# SenseBox-Eye_v1_3.net
KiCad netlist of a schematic drawn in EAGLE
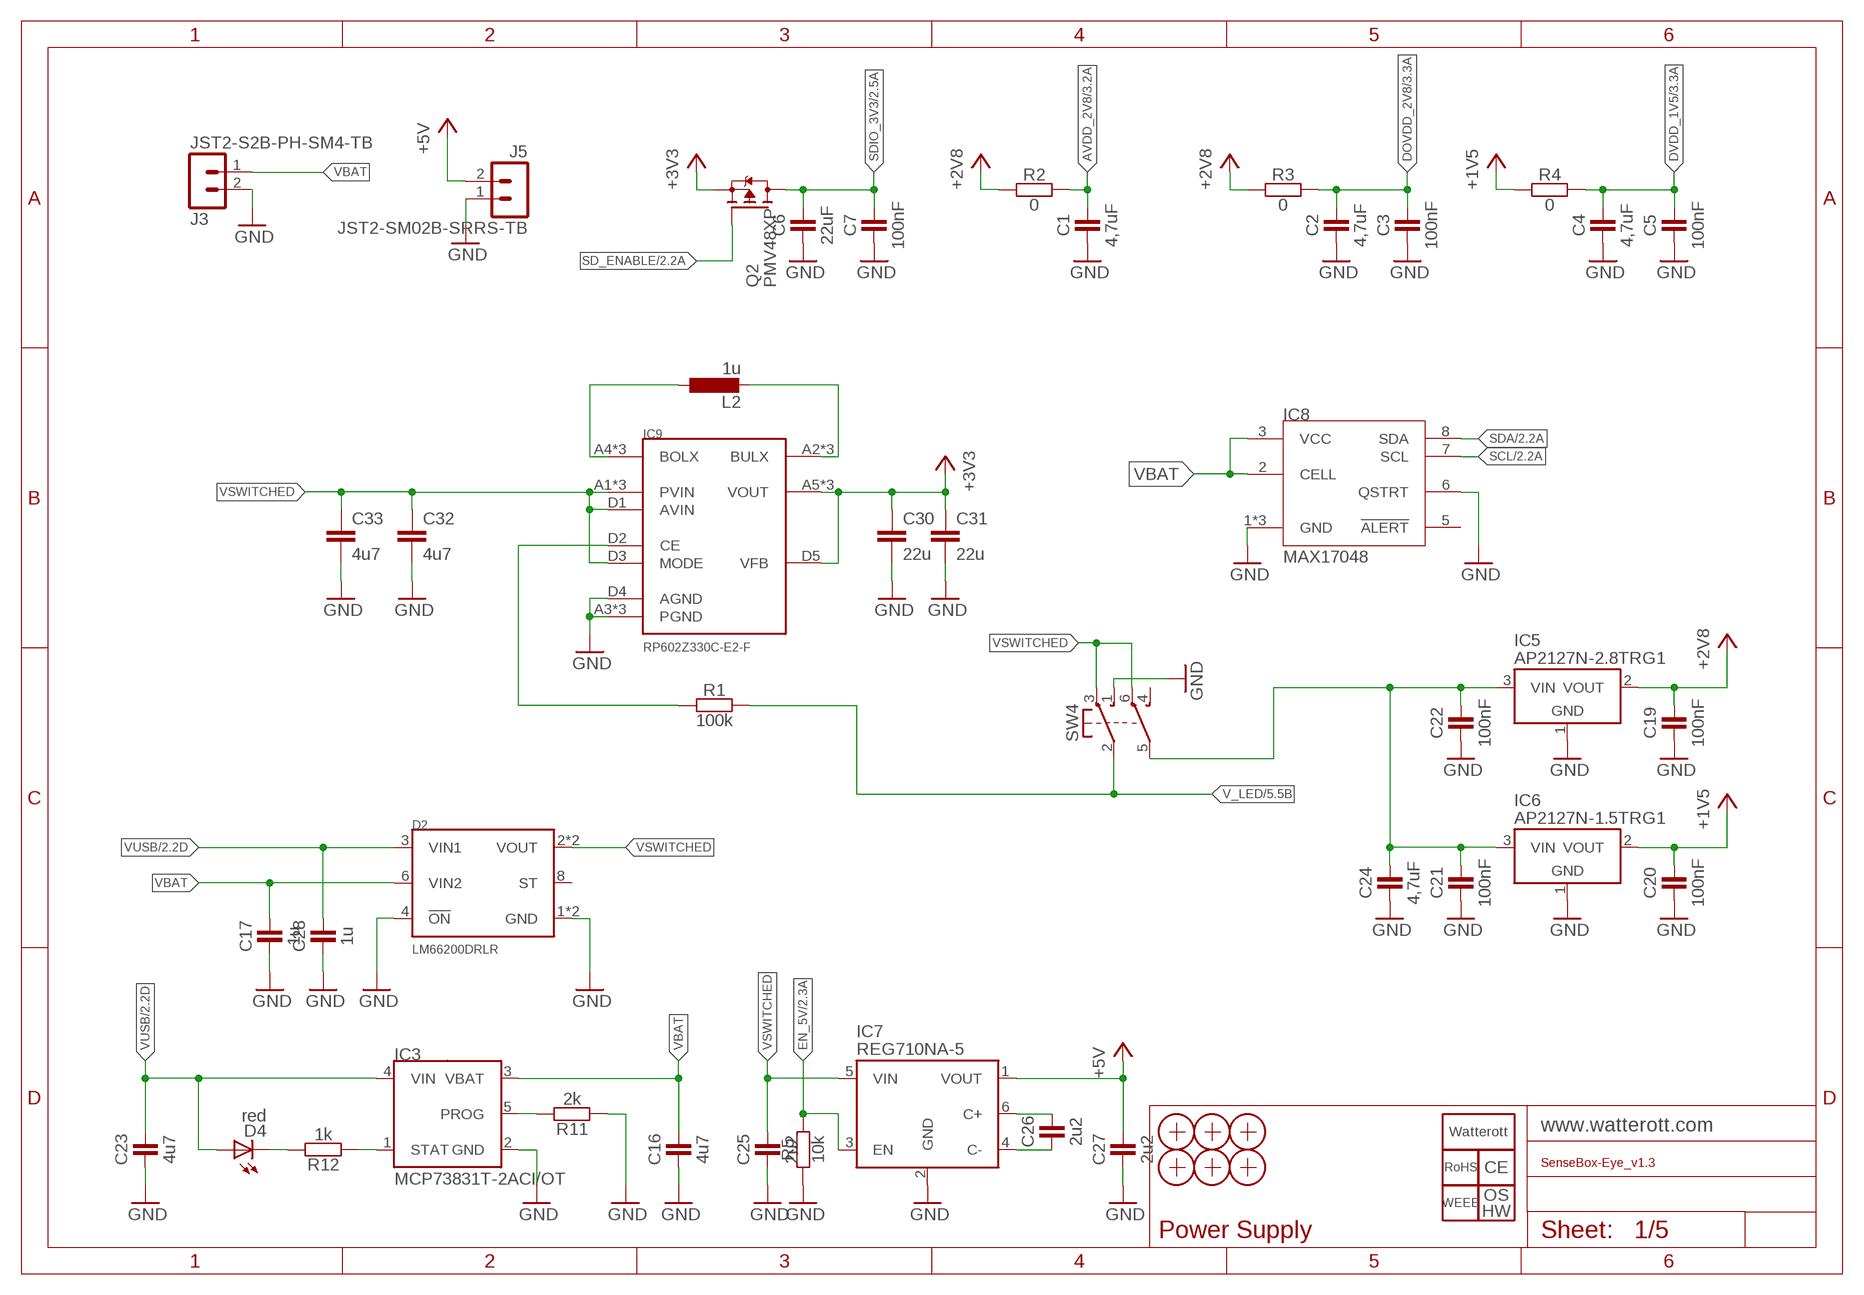
[diagram p0: schematic, sheet 1]
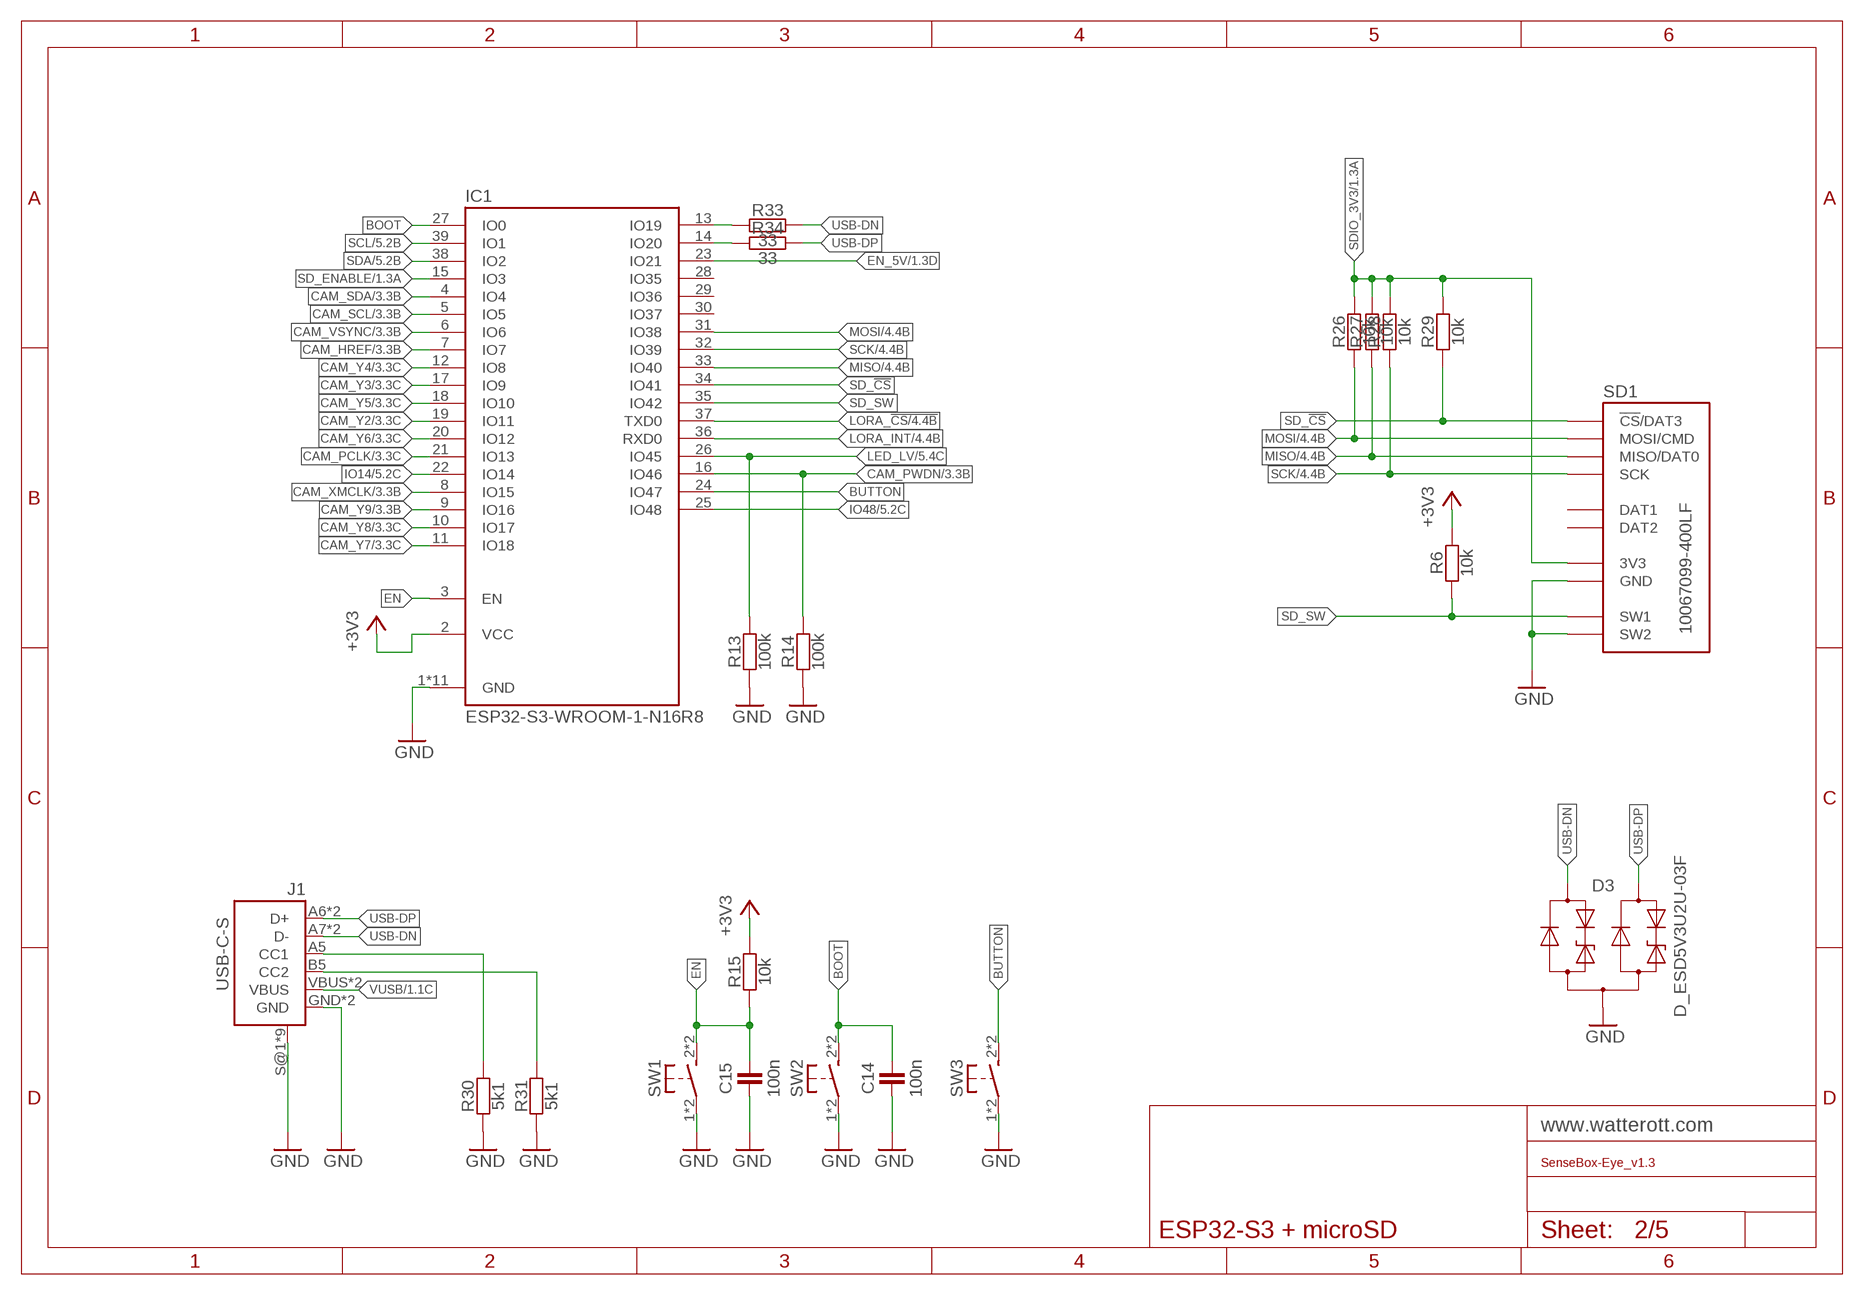
[diagram p1: schematic, sheet 2]
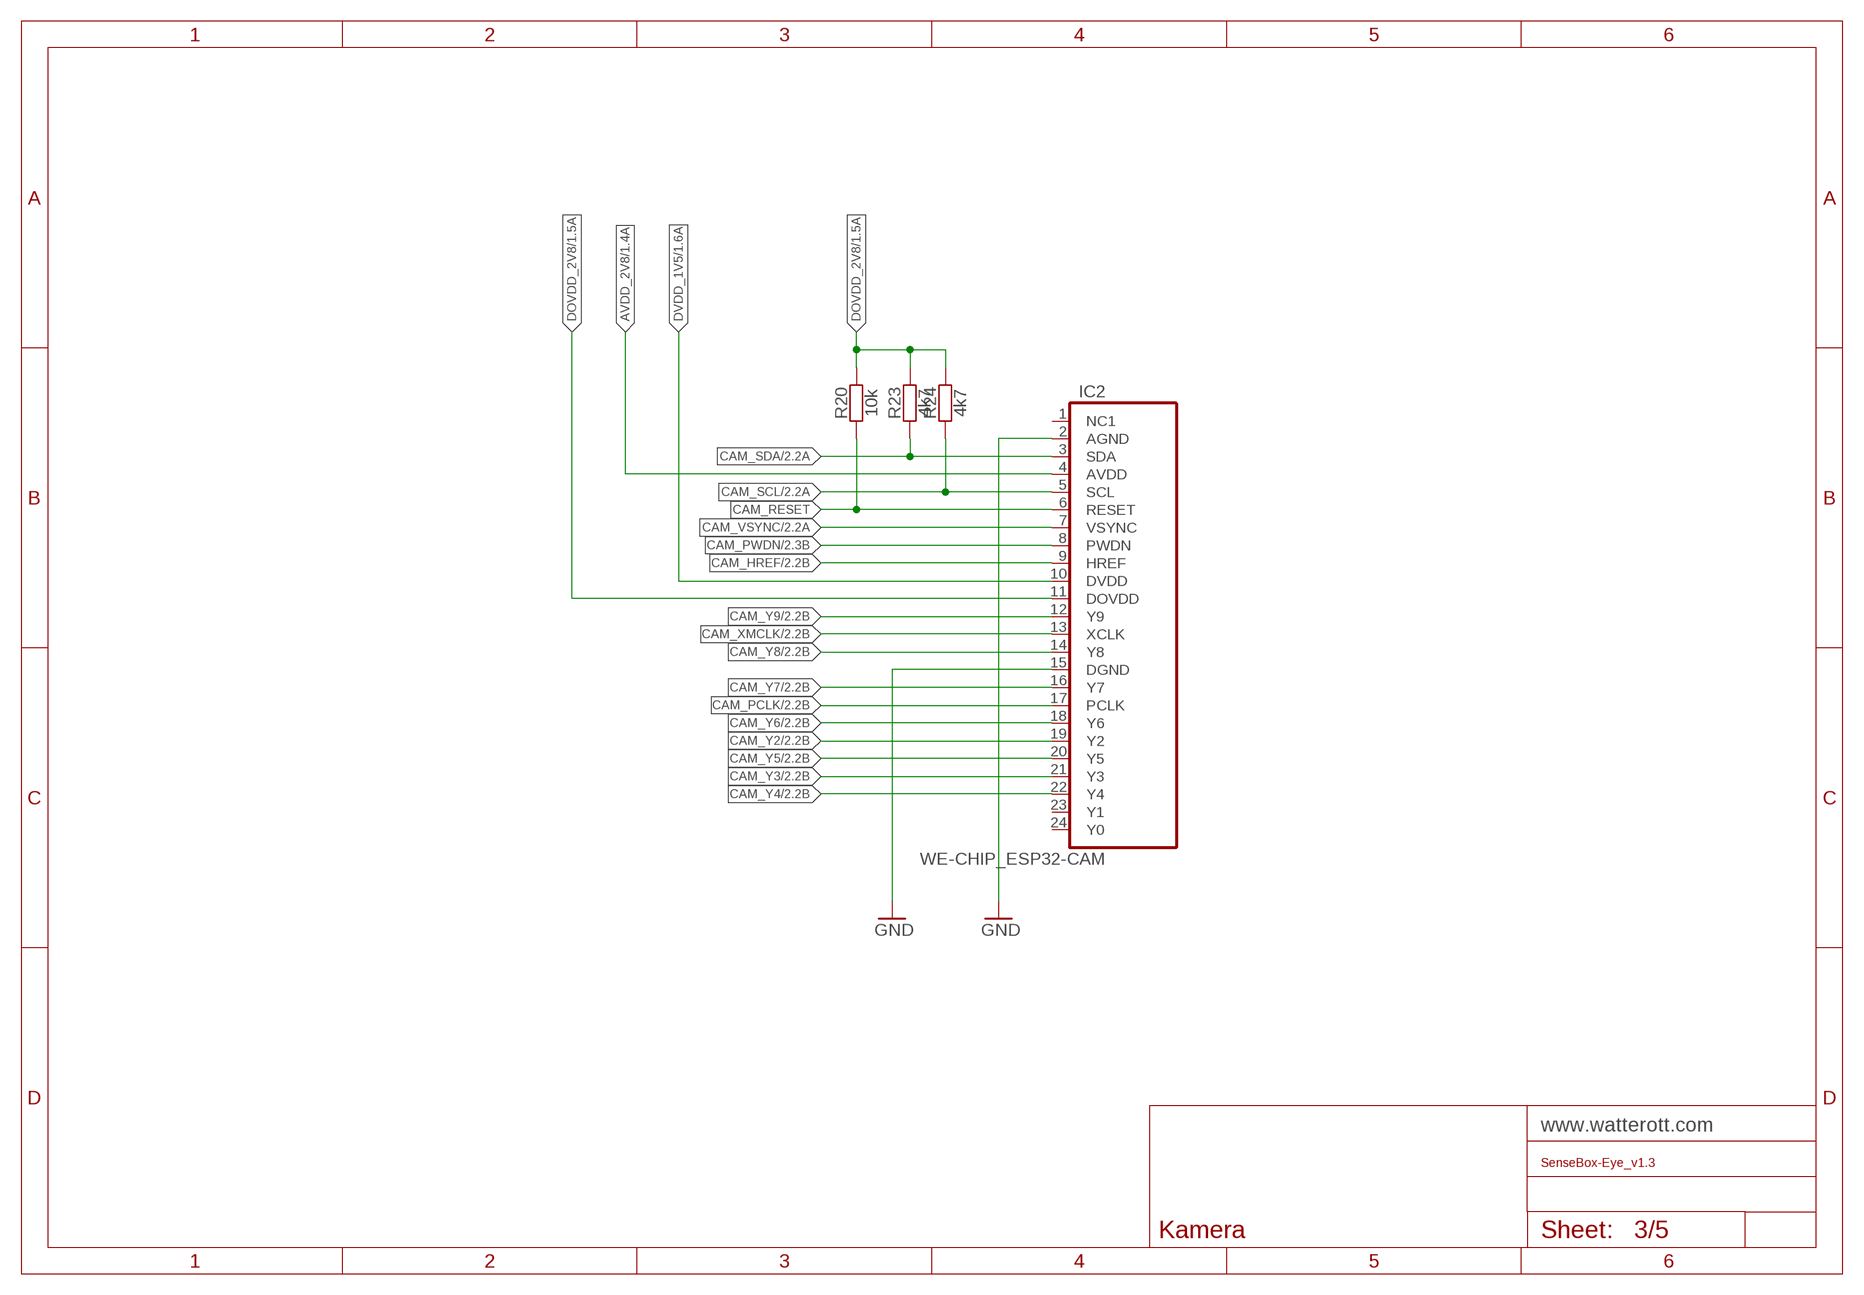
[diagram p2: schematic, sheet 3]
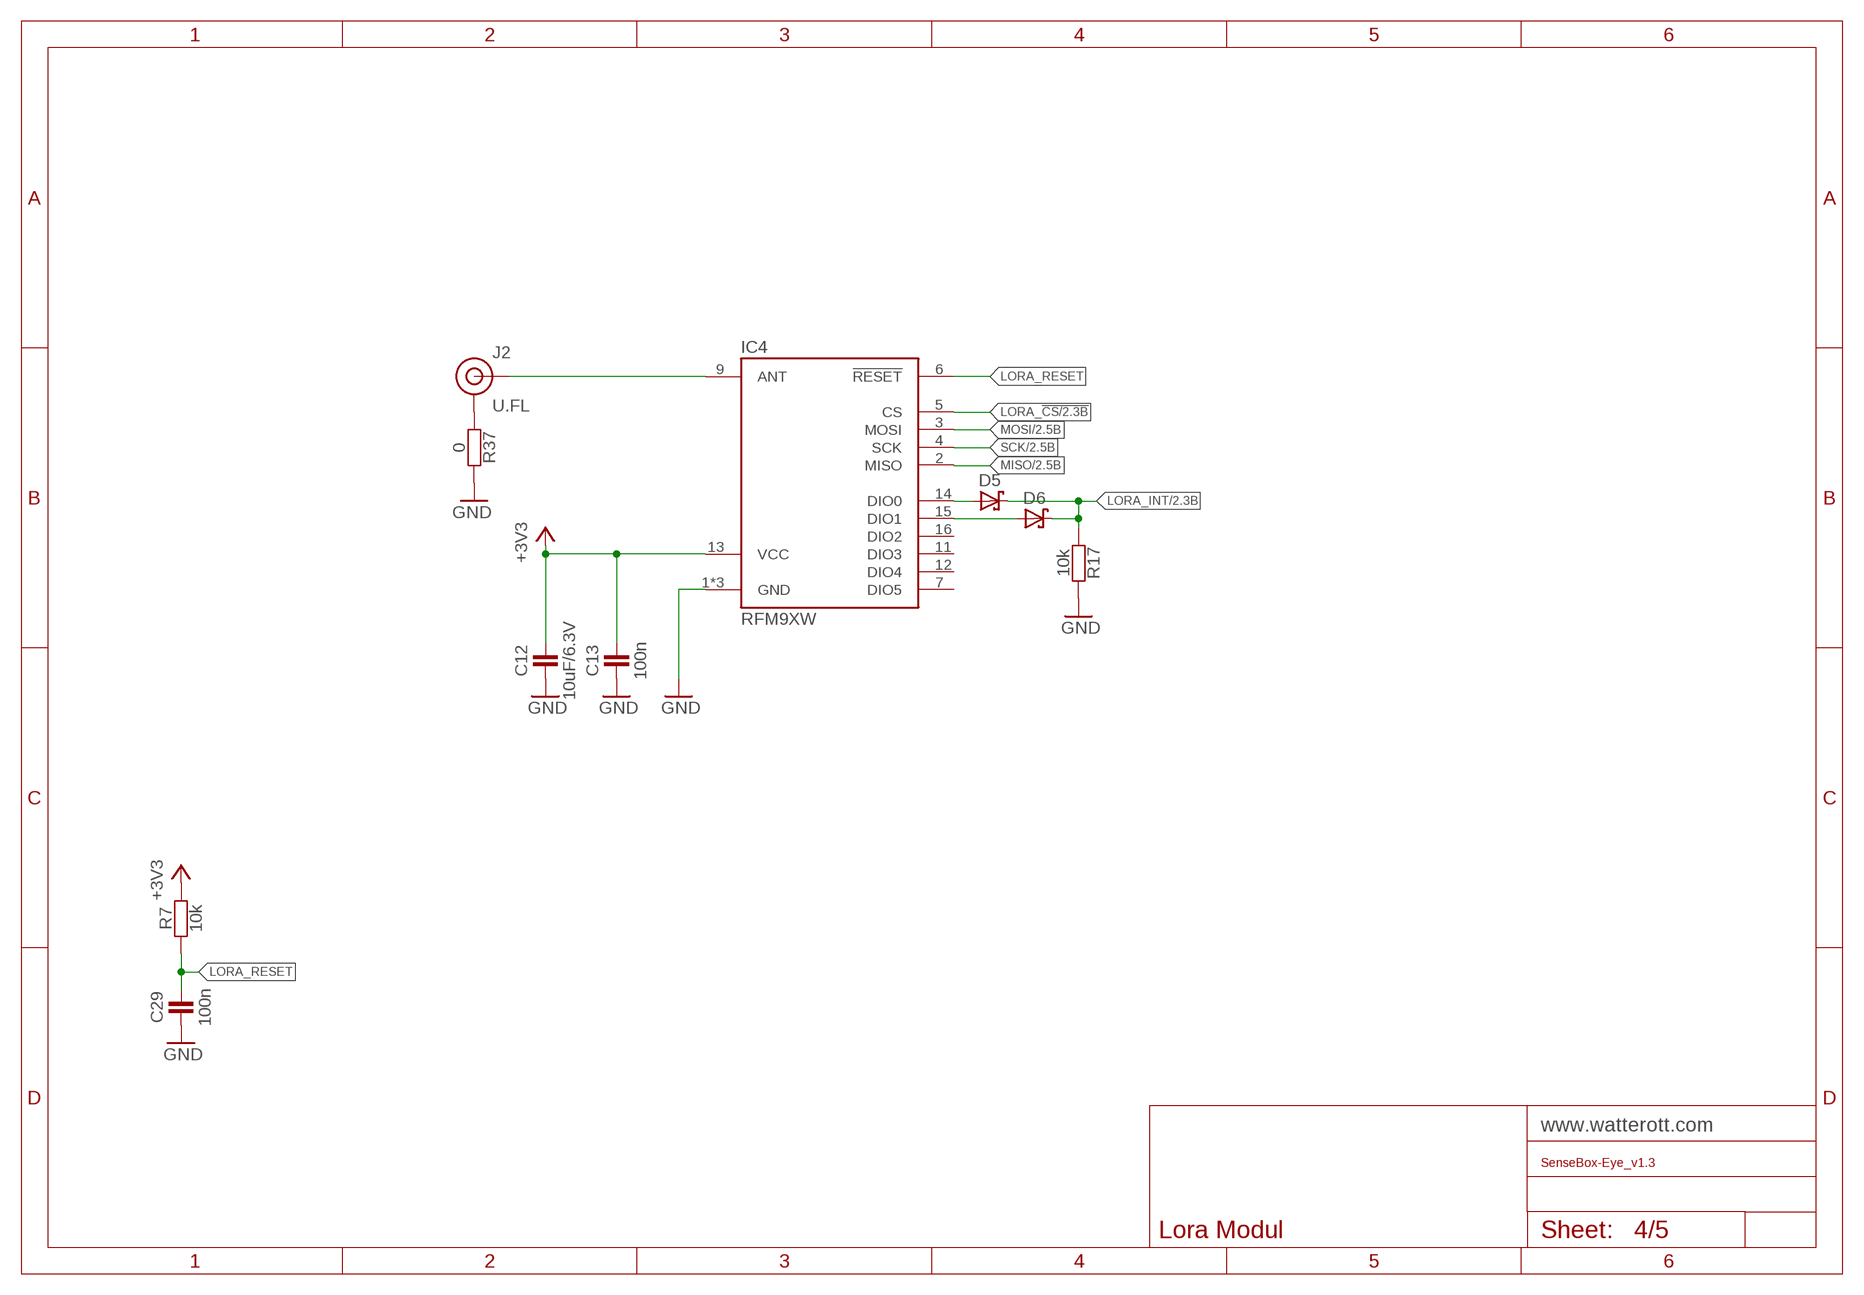
[diagram p3: schematic, sheet 4]
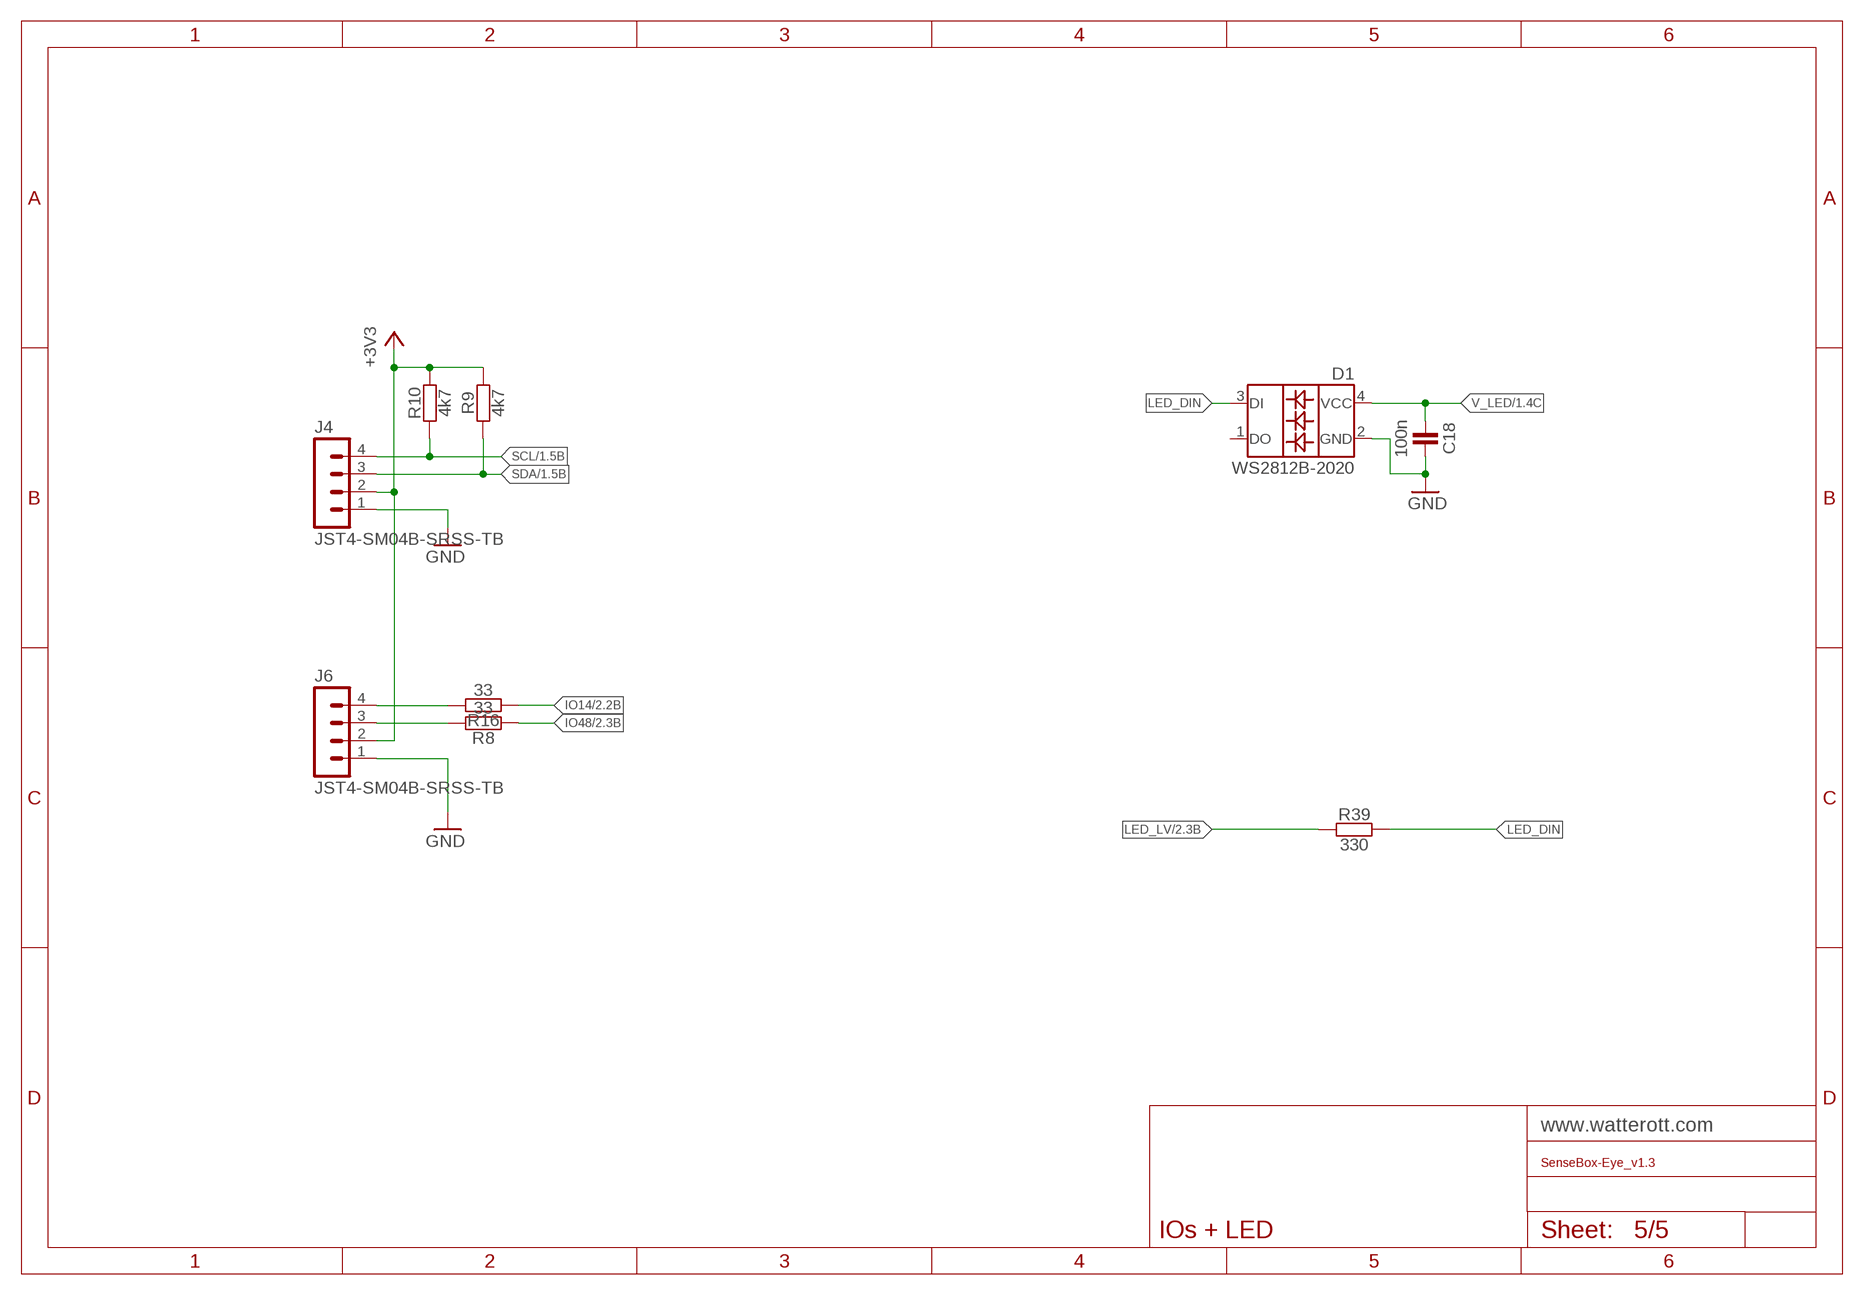
[diagram p4: schematic, sheet 5]

(export (version "E")
  (design (tool "Eeschema 10.0.6"))
  (components
    (comp (ref "C12")
      (value "10uF/6.3V")
      (footprint "eagle-import:C0402")
      (libsource (lib "eagle-import") (part "CAPACITOR-0402"))
    )
    (comp (ref "C13")
      (value "100n")
      (footprint "eagle-import:C0402")
      (libsource (lib "eagle-import") (part "CAPACITOR-0402"))
    )
    (comp (ref "C29")
      (value "100n")
      (footprint "eagle-import:C0402")
      (libsource (lib "eagle-import") (part "CAPACITOR-0402"))
    )
    (comp (ref "D5")
      (value "D_SCHOTTKY-SOD523")
      (footprint "eagle-import:SOD523")
      (libsource (lib "eagle-import") (part "D_SCHOTTKY-SOD523"))
    )
    (comp (ref "D6")
      (value "D_SCHOTTKY-SOD523")
      (footprint "eagle-import:SOD523")
      (libsource (lib "eagle-import") (part "D_SCHOTTKY-SOD523"))
    )
    (comp (ref "IC4")
      (value "RFM9XW")
      (footprint "eagle-import:RFM9X")
      (libsource (lib "eagle-import") (part "RFM9XW"))
    )
    (comp (ref "J2")
      (value "U.FL")
      (footprint "eagle-import:U.FL")
      (libsource (lib "eagle-import") (part "U.FL"))
    )
    (comp (ref "R7")
      (value "10k")
      (footprint "eagle-import:C0402")
      (libsource (lib "eagle-import") (part "RESISTOR-0402"))
    )
    (comp (ref "R17")
      (value "10k")
      (footprint "eagle-import:C0402")
      (libsource (lib "eagle-import") (part "RESISTOR-0402"))
    )
    (comp (ref "R37")
      (value "0")
      (footprint "eagle-import:C0402")
      (libsource (lib "eagle-import") (part "RESISTOR-0402"))
    )
    (comp (ref "C14")
      (value "100n")
      (footprint "eagle-import:C0402")
      (libsource (lib "eagle-import") (part "CAPACITOR-0402"))
    )
    (comp (ref "C15")
      (value "100n")
      (footprint "eagle-import:C0402")
      (libsource (lib "eagle-import") (part "CAPACITOR-0402"))
    )
    (comp (ref "D3")
      (value "D_ESD5V3U2U-03F")
      (footprint "eagle-import:SOT723")
      (libsource (lib "eagle-import") (part "D_ESD5V3U2U-03F"))
    )
    (comp (ref "IC1")
      (value "ESP32-S3-WROOM-1-N16R8")
      (footprint "eagle-import:ESP32-S3-WROOM-1")
      (libsource (lib "eagle-import") (part "ESP32_S3-WROOM-1"))
    )
    (comp (ref "J1")
      (value "USB-C-S")
      (footprint "eagle-import:USB-C-S")
      (libsource (lib "eagle-import") (part "USB-C-S"))
    )
    (comp (ref "R6")
      (value "10k")
      (footprint "eagle-import:C0402")
      (libsource (lib "eagle-import") (part "RESISTOR-0402"))
    )
    (comp (ref "R13")
      (value "100k")
      (footprint "eagle-import:C0402")
      (libsource (lib "eagle-import") (part "RESISTOR-0402"))
    )
    (comp (ref "R14")
      (value "100k")
      (footprint "eagle-import:C0402")
      (libsource (lib "eagle-import") (part "RESISTOR-0402"))
    )
    (comp (ref "R15")
      (value "10k")
      (footprint "eagle-import:C0402")
      (libsource (lib "eagle-import") (part "RESISTOR-0402"))
    )
    (comp (ref "R26")
      (value "10k")
      (footprint "eagle-import:C0402")
      (libsource (lib "eagle-import") (part "RESISTOR-0402"))
    )
    (comp (ref "R27")
      (value "10k")
      (footprint "eagle-import:C0402")
      (libsource (lib "eagle-import") (part "RESISTOR-0402"))
    )
    (comp (ref "R28")
      (value "10k")
      (footprint "eagle-import:C0402")
      (libsource (lib "eagle-import") (part "RESISTOR-0402"))
    )
    (comp (ref "R29")
      (value "10k")
      (footprint "eagle-import:C0402")
      (libsource (lib "eagle-import") (part "RESISTOR-0402"))
    )
    (comp (ref "R30")
      (value "5k1")
      (footprint "eagle-import:C0402")
      (libsource (lib "eagle-import") (part "RESISTOR-0402"))
    )
    (comp (ref "R31")
      (value "5k1")
      (footprint "eagle-import:C0402")
      (libsource (lib "eagle-import") (part "RESISTOR-0402"))
    )
    (comp (ref "R33")
      (value "33")
      (footprint "eagle-import:C0402")
      (libsource (lib "eagle-import") (part "RESISTOR-0402"))
    )
    (comp (ref "R34")
      (value "33")
      (footprint "eagle-import:C0402")
      (libsource (lib "eagle-import") (part "RESISTOR-0402"))
    )
    (comp (ref "SD1")
      (value "10067099-400LF")
      (footprint "eagle-import:SD_47309XXXX")
      (libsource (lib "eagle-import") (part "SD-CARD-MSD47"))
    )
    (comp (ref "SW1")
      (value "SW-TACTILE-TL3305")
      (footprint "eagle-import:TL3305")
      (libsource (lib "eagle-import") (part "SW-TACTILE-TL3305"))
    )
    (comp (ref "SW2")
      (value "SW-TACTILE-TL3305")
      (footprint "eagle-import:TL3305")
      (libsource (lib "eagle-import") (part "SW-TACTILE-TL3305"))
    )
    (comp (ref "SW3")
      (value "SW-TACTILE-TL3305")
      (footprint "eagle-import:TL3305")
      (libsource (lib "eagle-import") (part "SW-TACTILE-TL3305"))
    )
    (comp (ref "C18")
      (value "100n")
      (footprint "eagle-import:C0402")
      (libsource (lib "eagle-import") (part "CAPACITOR-0402"))
    )
    (comp (ref "D1")
      (value "WS2812B-2020")
      (footprint "eagle-import:WS2812_2020")
      (libsource (lib "eagle-import") (part "WS2812B-2020"))
    )
    (comp (ref "J4")
      (value "JST4-SM04B-SRSS-TB")
      (footprint "eagle-import:JST_SM04B-SRSS-TB")
      (libsource (lib "eagle-import") (part "JST4-SM04B-SRSS-TB"))
    )
    (comp (ref "J6")
      (value "JST4-SM04B-SRSS-TB")
      (footprint "eagle-import:JST_SM04B-SRSS-TB")
      (libsource (lib "eagle-import") (part "JST4-SM04B-SRSS-TB"))
    )
    (comp (ref "R8")
      (value "33")
      (footprint "eagle-import:C0402")
      (libsource (lib "eagle-import") (part "RESISTOR-0402"))
    )
    (comp (ref "R9")
      (value "4k7")
      (footprint "eagle-import:C0402")
      (libsource (lib "eagle-import") (part "RESISTOR-0402"))
    )
    (comp (ref "R10")
      (value "4k7")
      (footprint "eagle-import:C0402")
      (libsource (lib "eagle-import") (part "RESISTOR-0402"))
    )
    (comp (ref "R16")
      (value "33")
      (footprint "eagle-import:C0402")
      (libsource (lib "eagle-import") (part "RESISTOR-0402"))
    )
    (comp (ref "R39")
      (value "330")
      (footprint "eagle-import:C0402")
      (libsource (lib "eagle-import") (part "RESISTOR-0402"))
    )
    (comp (ref "IC2")
      (value "WE-CHIP_ESP32-CAM")
      (footprint "eagle-import:WE-CHIP_FPC24-0.5-CAM")
      (libsource (lib "eagle-import") (part "WE-CHIP_ESP32-CAM"))
    )
    (comp (ref "R20")
      (value "10k")
      (footprint "eagle-import:C0402")
      (libsource (lib "eagle-import") (part "RESISTOR-0402"))
    )
    (comp (ref "R23")
      (value "4k7")
      (footprint "eagle-import:C0402")
      (libsource (lib "eagle-import") (part "RESISTOR-0402"))
    )
    (comp (ref "R24")
      (value "4k7")
      (footprint "eagle-import:C0402")
      (libsource (lib "eagle-import") (part "RESISTOR-0402"))
    )
    (comp (ref "C1")
      (value "4,7uF")
      (footprint "eagle-import:C0402")
      (libsource (lib "eagle-import") (part "CAPACITOR-0402"))
    )
    (comp (ref "C2")
      (value "4,7uF")
      (footprint "eagle-import:C0402")
      (libsource (lib "eagle-import") (part "CAPACITOR-0402"))
    )
    (comp (ref "C3")
      (value "100nF")
      (footprint "eagle-import:C0402")
      (libsource (lib "eagle-import") (part "CAPACITOR-0402"))
    )
    (comp (ref "C4")
      (value "4,7uF")
      (footprint "eagle-import:C0402")
      (libsource (lib "eagle-import") (part "CAPACITOR-0402"))
    )
    (comp (ref "C5")
      (value "100nF")
      (footprint "eagle-import:C0402")
      (libsource (lib "eagle-import") (part "CAPACITOR-0402"))
    )
    (comp (ref "C6")
      (value "22uF")
      (footprint "eagle-import:C0402")
      (libsource (lib "eagle-import") (part "CAPACITOR-0402"))
    )
    (comp (ref "C7")
      (value "100nF")
      (footprint "eagle-import:C0402")
      (libsource (lib "eagle-import") (part "CAPACITOR-0402"))
    )
    (comp (ref "C16")
      (value "4u7")
      (footprint "eagle-import:C0402")
      (libsource (lib "eagle-import") (part "CAPACITOR-0402"))
    )
    (comp (ref "C17")
      (value "1u")
      (footprint "eagle-import:C0402")
      (libsource (lib "eagle-import") (part "CAPACITOR-0402"))
    )
    (comp (ref "C19")
      (value "100nF")
      (footprint "eagle-import:C0402")
      (libsource (lib "eagle-import") (part "CAPACITOR-0402"))
    )
    (comp (ref "C20")
      (value "100nF")
      (footprint "eagle-import:C0402")
      (libsource (lib "eagle-import") (part "CAPACITOR-0402"))
    )
    (comp (ref "C21")
      (value "100nF")
      (footprint "eagle-import:C0402")
      (libsource (lib "eagle-import") (part "CAPACITOR-0402"))
    )
    (comp (ref "C22")
      (value "100nF")
      (footprint "eagle-import:C0402")
      (libsource (lib "eagle-import") (part "CAPACITOR-0402"))
    )
    (comp (ref "C23")
      (value "4u7")
      (footprint "eagle-import:C0402")
      (libsource (lib "eagle-import") (part "CAPACITOR-0402"))
    )
    (comp (ref "C24")
      (value "4,7uF")
      (footprint "eagle-import:C0402")
      (libsource (lib "eagle-import") (part "CAPACITOR-0402"))
    )
    (comp (ref "C25")
      (value "2u2")
      (footprint "eagle-import:C0402")
      (libsource (lib "eagle-import") (part "CAPACITOR-0402"))
    )
    (comp (ref "C26")
      (value "2u2")
      (footprint "eagle-import:C0402")
      (libsource (lib "eagle-import") (part "CAPACITOR-0402"))
    )
    (comp (ref "C27")
      (value "2u2")
      (footprint "eagle-import:C0402")
      (libsource (lib "eagle-import") (part "CAPACITOR-0402"))
    )
    (comp (ref "C28")
      (value "1u")
      (footprint "eagle-import:C0402")
      (libsource (lib "eagle-import") (part "CAPACITOR-0402"))
    )
    (comp (ref "C30")
      (value "22u")
      (footprint "eagle-import:0805N")
      (fields (field (name "VOLTAGE") "6V3"))
      (libsource (lib "eagle-import") (part "C_0805N_22U"))
    )
    (comp (ref "C31")
      (value "22u")
      (footprint "eagle-import:0805N")
      (fields (field (name "VOLTAGE") "6V3"))
      (libsource (lib "eagle-import") (part "C_0805N_22U"))
    )
    (comp (ref "C32")
      (value "4u7")
      (footprint "eagle-import:0603N")
      (fields (field (name "VOLTAGE") "6V3"))
      (libsource (lib "eagle-import") (part "C_0603N_4U7"))
    )
    (comp (ref "C33")
      (value "4u7")
      (footprint "eagle-import:0603N")
      (fields (field (name "VOLTAGE") "6V3"))
      (libsource (lib "eagle-import") (part "C_0603N_4U7"))
    )
    (comp (ref "D2")
      (value "LM66200DRLR")
      (footprint "eagle-import:SOT-5X3")
      (libsource (lib "eagle-import") (part "LM66200"))
    )
    (comp (ref "D4")
      (value "red")
      (footprint "eagle-import:0603N")
      (libsource (lib "eagle-import") (part "LED_0603N_RED"))
    )
    (comp (ref "IC3")
      (value "MCP73831T-2ACI/OT")
      (footprint "eagle-import:SOT23-5")
      (libsource (lib "eagle-import") (part "MCP73831_SOT23-5_MCP73831T-2ACI/OT"))
    )
    (comp (ref "IC5")
      (value "AP2127N-2.8TRG1")
      (footprint "eagle-import:SOT23")
      (libsource (lib "eagle-import") (part "VREG-TS9011-3V3"))
    )
    (comp (ref "IC6")
      (value "AP2127N-1.5TRG1")
      (footprint "eagle-import:SOT23")
      (libsource (lib "eagle-import") (part "VREG-TS9011-3V3"))
    )
    (comp (ref "IC7")
      (value "REG710NA-5")
      (footprint "eagle-import:SOT23-6")
      (libsource (lib "eagle-import") (part "REG710NA-5"))
    )
    (comp (ref "IC8")
      (value "MAX17048")
      (footprint "eagle-import:UDFN8_2020")
      (libsource (lib "eagle-import") (part "MAX1704X"))
    )
    (comp (ref "IC9")
      (value "RP602Z330C-E2-F")
      (footprint "eagle-import:WLCSP-20-P1")
      (libsource (lib "eagle-import") (part "RP602_WLCSP-20-P1_RP602Z330C-E2-F"))
    )
    (comp (ref "J3")
      (value "JST2-S2B-PH-SM4-TB")
      (footprint "eagle-import:JST_S2B-PH-SM4-TB")
      (libsource (lib "eagle-import") (part "JST2-S2B-PH-SM4-TB"))
    )
    (comp (ref "J5")
      (value "JST2-SM02B-SRRS-TB")
      (footprint "eagle-import:JST_SM02B-SRSS-TB")
      (libsource (lib "eagle-import") (part "JST2-SM02B-SRRS-TB"))
    )
    (comp (ref "L2")
      (value "1u")
      (footprint "eagle-import:5040")
      (libsource (lib "eagle-import") (part "L_5040_WE-LQS-1U"))
    )
    (comp (ref "LOGO2")
      (value "LOGO_CE-2")
      (footprint "eagle-import:CE_2MM")
      (libsource (lib "eagle-import") (part "LOGO_CE-2"))
    )
    (comp (ref "LOGO3")
      (value "LOGO_OSHW-2")
      (footprint "eagle-import:OSHW_2MM")
      (libsource (lib "eagle-import") (part "LOGO_OSHW-2"))
    )
    (comp (ref "LOGO4")
      (value "LOGO_ROHS-2")
      (footprint "eagle-import:ROHS_2MM")
      (libsource (lib "eagle-import") (part "LOGO_ROHS-2"))
    )
    (comp (ref "LOGO5")
      (value "LOGO_WEEE-4")
      (footprint "eagle-import:WEEE_4MM")
      (libsource (lib "eagle-import") (part "LOGO_WEEE-4"))
    )
    (comp (ref "LOGO6")
      (value "LOGO_SPARK-2")
      (footprint "eagle-import:SPARK_2MM")
      (libsource (lib "eagle-import") (part "LOGO_SPARK-2"))
    )
    (comp (ref "Q2")
      (value "PMV48XP")
      (footprint "eagle-import:SOT23")
      (fields (field (name "VOLTAGE") "20"))
      (libsource (lib "eagle-import") (part "MOSFET-P_SOT23'_PMV48XP"))
    )
    (comp (ref "R1")
      (value "100k")
      (footprint "eagle-import:C0402")
      (libsource (lib "eagle-import") (part "RESISTOR-0402"))
    )
    (comp (ref "R2")
      (value "0")
      (footprint "eagle-import:C0402")
      (libsource (lib "eagle-import") (part "RESISTOR-0402"))
    )
    (comp (ref "R3")
      (value "0")
      (footprint "eagle-import:C0402")
      (libsource (lib "eagle-import") (part "RESISTOR-0402"))
    )
    (comp (ref "R4")
      (value "0")
      (footprint "eagle-import:C0402")
      (libsource (lib "eagle-import") (part "RESISTOR-0402"))
    )
    (comp (ref "R5")
      (value "10k")
      (footprint "eagle-import:C0402")
      (libsource (lib "eagle-import") (part "RESISTOR-0402"))
    )
    (comp (ref "R11")
      (value "2k")
      (footprint "eagle-import:C0402")
      (libsource (lib "eagle-import") (part "RESISTOR-0402"))
    )
    (comp (ref "R12")
      (value "1k")
      (footprint "eagle-import:C0402")
      (libsource (lib "eagle-import") (part "RESISTOR-0402"))
    )
    (comp (ref "SW4")
      (value "SW-2UM-CUS22B")
      (footprint "eagle-import:CUS22B")
      (libsource (lib "eagle-import") (part "SW-2UM-CUS22B"))
    )
    (comp (ref "X1")
      (value "PASSER-04")
      (footprint "eagle-import:PASSER_04MM")
      (libsource (lib "eagle-import") (part "PASSER-04"))
    )
    (comp (ref "X2")
      (value "PASSER-04")
      (footprint "eagle-import:PASSER_04MM")
      (libsource (lib "eagle-import") (part "PASSER-04"))
    )
    (comp (ref "X3")
      (value "PASSER-04")
      (footprint "eagle-import:PASSER_04MM")
      (libsource (lib "eagle-import") (part "PASSER-04"))
    )
    (comp (ref "X4")
      (value "PASSER-04")
      (footprint "eagle-import:PASSER_04MM")
      (libsource (lib "eagle-import") (part "PASSER-04"))
    )
    (comp (ref "X5")
      (value "PASSER-04")
      (footprint "eagle-import:PASSER_04MM")
      (libsource (lib "eagle-import") (part "PASSER-04"))
    )
    (comp (ref "X6")
      (value "PASSER-04")
      (footprint "eagle-import:PASSER_04MM")
      (libsource (lib "eagle-import") (part "PASSER-04"))
    )
  )
  (nets
    (net (code "1") (name "+1V5") (class "Default")
      (node (ref "C20") (pin "2") (pinfunction "2_2") (pintype "passive"))
      (node (ref "IC6") (pin "2") (pinfunction "VOUT_2") (pintype "power_in"))
      (node (ref "R4") (pin "1") (pinfunction "1_1") (pintype "passive"))
    )
    (net (code "2") (name "+2V8") (class "Default")
      (node (ref "C19") (pin "2") (pinfunction "2_2") (pintype "passive"))
      (node (ref "IC5") (pin "2") (pinfunction "VOUT_2") (pintype "power_in"))
      (node (ref "R2") (pin "1") (pinfunction "1_1") (pintype "passive"))
      (node (ref "R3") (pin "1") (pinfunction "1_1") (pintype "passive"))
    )
    (net (code "3") (name "+3V3") (class "Default")
      (node (ref "C12") (pin "2") (pinfunction "2_2") (pintype "passive"))
      (node (ref "C13") (pin "2") (pinfunction "2_2") (pintype "passive"))
      (node (ref "C30") (pin "1") (pinfunction "1_1") (pintype "passive"))
      (node (ref "C31") (pin "1") (pinfunction "1_1") (pintype "passive"))
      (node (ref "IC1") (pin "2") (pinfunction "VCC_2") (pintype "power_in"))
      (node (ref "IC4") (pin "13") (pinfunction "VCC_13") (pintype "power_in"))
      (node (ref "IC9") (pin "A5") (pinfunction "VOUT_A5") (pintype "power_in"))
      (node (ref "IC9") (pin "B5") (pinfunction "VOUT_B5") (pintype "power_in"))
      (node (ref "IC9") (pin "C5") (pinfunction "VOUT_C5") (pintype "power_in"))
      (node (ref "IC9") (pin "D5") (pinfunction "VFB_D5") (pintype "input"))
      (node (ref "J4") (pin "2") (pinfunction "2_2") (pintype "passive"))
      (node (ref "J6") (pin "2") (pinfunction "2_2") (pintype "passive"))
      (node (ref "Q2") (pin "2") (pinfunction "S_2") (pintype "passive"))
      (node (ref "R10") (pin "1") (pinfunction "1_1") (pintype "passive"))
      (node (ref "R15") (pin "2") (pinfunction "2_2") (pintype "passive"))
      (node (ref "R6") (pin "2") (pinfunction "2_2") (pintype "passive"))
      (node (ref "R7") (pin "2") (pinfunction "2_2") (pintype "passive"))
      (node (ref "R9") (pin "1") (pinfunction "1_1") (pintype "passive"))
    )
    (net (code "4") (name "+5V") (class "Default")
      (node (ref "C27") (pin "2") (pinfunction "2_2") (pintype "passive"))
      (node (ref "IC7") (pin "1") (pinfunction "VOUT_1") (pintype "power_in"))
      (node (ref "J5") (pin "2") (pinfunction "2_2") (pintype "passive"))
    )
    (net (code "5") (name "AVDD_2V8") (class "Default")
      (node (ref "C1") (pin "2") (pinfunction "2_2") (pintype "passive"))
      (node (ref "IC2") (pin "4") (pinfunction "AVDD_4") (pintype "bidirectional"))
      (node (ref "R2") (pin "2") (pinfunction "2_2") (pintype "passive"))
    )
    (net (code "6") (name "BOOT") (class "Default")
      (node (ref "C14") (pin "2") (pinfunction "2_2") (pintype "passive"))
      (node (ref "IC1") (pin "27") (pinfunction "IO0_27") (pintype "bidirectional"))
      (node (ref "SW2") (pin "2") (pinfunction "S1_2") (pintype "passive"))
      (node (ref "SW2") (pin "3") (pinfunction "S1_3") (pintype "passive"))
    )
    (net (code "7") (name "BUTTON") (class "Default")
      (node (ref "IC1") (pin "24") (pinfunction "IO47_24") (pintype "bidirectional"))
      (node (ref "SW3") (pin "2") (pinfunction "S1_2") (pintype "passive"))
      (node (ref "SW3") (pin "3") (pinfunction "S1_3") (pintype "passive"))
    )
    (net (code "8") (name "CAM_HREF") (class "Default")
      (node (ref "IC1") (pin "7") (pinfunction "IO7_7") (pintype "bidirectional"))
      (node (ref "IC2") (pin "9") (pinfunction "HREF_9") (pintype "bidirectional"))
    )
    (net (code "9") (name "CAM_PCLK") (class "Default")
      (node (ref "IC1") (pin "21") (pinfunction "IO13_21") (pintype "bidirectional"))
      (node (ref "IC2") (pin "17") (pinfunction "PCLK_17") (pintype "bidirectional"))
    )
    (net (code "10") (name "CAM_PWDN") (class "Default")
      (node (ref "IC1") (pin "16") (pinfunction "IO46_16") (pintype "bidirectional"))
      (node (ref "IC2") (pin "8") (pinfunction "PWDN_8") (pintype "bidirectional"))
      (node (ref "R14") (pin "2") (pinfunction "2_2") (pintype "passive"))
    )
    (net (code "11") (name "CAM_RESET") (class "Default")
      (node (ref "IC2") (pin "6") (pinfunction "RESET_6") (pintype "bidirectional"))
      (node (ref "R20") (pin "1") (pinfunction "1_1") (pintype "passive"))
    )
    (net (code "12") (name "CAM_SCL") (class "Default")
      (node (ref "IC1") (pin "5") (pinfunction "IO5_5") (pintype "bidirectional"))
      (node (ref "IC2") (pin "5") (pinfunction "SCL_5") (pintype "bidirectional"))
      (node (ref "R24") (pin "1") (pinfunction "1_1") (pintype "passive"))
    )
    (net (code "13") (name "CAM_SDA") (class "Default")
      (node (ref "IC1") (pin "4") (pinfunction "IO4_4") (pintype "bidirectional"))
      (node (ref "IC2") (pin "3") (pinfunction "SDA_3") (pintype "bidirectional"))
      (node (ref "R23") (pin "1") (pinfunction "1_1") (pintype "passive"))
    )
    (net (code "14") (name "CAM_VSYNC") (class "Default")
      (node (ref "IC1") (pin "6") (pinfunction "IO6_6") (pintype "bidirectional"))
      (node (ref "IC2") (pin "7") (pinfunction "VSYNC_7") (pintype "bidirectional"))
    )
    (net (code "15") (name "CAM_XMCLK") (class "Default")
      (node (ref "IC1") (pin "8") (pinfunction "IO15_8") (pintype "bidirectional"))
      (node (ref "IC2") (pin "13") (pinfunction "XCLK_13") (pintype "bidirectional"))
    )
    (net (code "16") (name "CAM_Y2") (class "Default")
      (node (ref "IC1") (pin "19") (pinfunction "IO11_19") (pintype "bidirectional"))
      (node (ref "IC2") (pin "19") (pinfunction "Y2_19") (pintype "bidirectional"))
    )
    (net (code "17") (name "CAM_Y3") (class "Default")
      (node (ref "IC1") (pin "17") (pinfunction "IO9_17") (pintype "bidirectional"))
      (node (ref "IC2") (pin "21") (pinfunction "Y3_21") (pintype "bidirectional"))
    )
    (net (code "18") (name "CAM_Y4") (class "Default")
      (node (ref "IC1") (pin "12") (pinfunction "IO8_12") (pintype "bidirectional"))
      (node (ref "IC2") (pin "22") (pinfunction "Y4_22") (pintype "bidirectional"))
    )
    (net (code "19") (name "CAM_Y5") (class "Default")
      (node (ref "IC1") (pin "18") (pinfunction "IO10_18") (pintype "bidirectional"))
      (node (ref "IC2") (pin "20") (pinfunction "Y5_20") (pintype "bidirectional"))
    )
    (net (code "20") (name "CAM_Y6") (class "Default")
      (node (ref "IC1") (pin "20") (pinfunction "IO12_20") (pintype "bidirectional"))
      (node (ref "IC2") (pin "18") (pinfunction "Y6_18") (pintype "bidirectional"))
    )
    (net (code "21") (name "CAM_Y7") (class "Default")
      (node (ref "IC1") (pin "11") (pinfunction "IO18_11") (pintype "bidirectional"))
      (node (ref "IC2") (pin "16") (pinfunction "Y7_16") (pintype "bidirectional"))
    )
    (net (code "22") (name "CAM_Y8") (class "Default")
      (node (ref "IC1") (pin "10") (pinfunction "IO17_10") (pintype "bidirectional"))
      (node (ref "IC2") (pin "14") (pinfunction "Y8_14") (pintype "bidirectional"))
    )
    (net (code "23") (name "CAM_Y9") (class "Default")
      (node (ref "IC1") (pin "9") (pinfunction "IO16_9") (pintype "bidirectional"))
      (node (ref "IC2") (pin "12") (pinfunction "Y9_12") (pintype "bidirectional"))
    )
    (net (code "24") (name "DOVDD_2V8") (class "Default")
      (node (ref "C2") (pin "2") (pinfunction "2_2") (pintype "passive"))
      (node (ref "C3") (pin "2") (pinfunction "2_2") (pintype "passive"))
      (node (ref "IC2") (pin "11") (pinfunction "DOVDD_11") (pintype "bidirectional"))
      (node (ref "R20") (pin "2") (pinfunction "2_2") (pintype "passive"))
      (node (ref "R23") (pin "2") (pinfunction "2_2") (pintype "passive"))
      (node (ref "R24") (pin "2") (pinfunction "2_2") (pintype "passive"))
      (node (ref "R3") (pin "2") (pinfunction "2_2") (pintype "passive"))
    )
    (net (code "25") (name "DVDD_1V5") (class "Default")
      (node (ref "C4") (pin "2") (pinfunction "2_2") (pintype "passive"))
      (node (ref "C5") (pin "2") (pinfunction "2_2") (pintype "passive"))
      (node (ref "IC2") (pin "10") (pinfunction "DVDD_10") (pintype "bidirectional"))
      (node (ref "R4") (pin "2") (pinfunction "2_2") (pintype "passive"))
    )
    (net (code "26") (name "EN") (class "Default")
      (node (ref "C15") (pin "2") (pinfunction "2_2") (pintype "passive"))
      (node (ref "IC1") (pin "3") (pinfunction "EN_3") (pintype "bidirectional"))
      (node (ref "R15") (pin "1") (pinfunction "1_1") (pintype "passive"))
      (node (ref "SW1") (pin "2") (pinfunction "S1_2") (pintype "passive"))
      (node (ref "SW1") (pin "3") (pinfunction "S1_3") (pintype "passive"))
    )
    (net (code "27") (name "EN_5V") (class "Default")
      (node (ref "IC1") (pin "23") (pinfunction "IO21_23") (pintype "bidirectional"))
      (node (ref "IC7") (pin "3") (pinfunction "EN_3") (pintype "passive"))
      (node (ref "R5") (pin "2") (pinfunction "2_2") (pintype "passive"))
    )
    (net (code "28") (name "GND") (class "Default")
      (node (ref "C1") (pin "1") (pinfunction "1_1") (pintype "passive"))
      (node (ref "C12") (pin "1") (pinfunction "1_1") (pintype "passive"))
      (node (ref "C13") (pin "1") (pinfunction "1_1") (pintype "passive"))
      (node (ref "C14") (pin "1") (pinfunction "1_1") (pintype "passive"))
      (node (ref "C15") (pin "1") (pinfunction "1_1") (pintype "passive"))
      (node (ref "C16") (pin "1") (pinfunction "1_1") (pintype "passive"))
      (node (ref "C17") (pin "1") (pinfunction "1_1") (pintype "passive"))
      (node (ref "C18") (pin "1") (pinfunction "1_1") (pintype "passive"))
      (node (ref "C19") (pin "1") (pinfunction "1_1") (pintype "passive"))
      (node (ref "C2") (pin "1") (pinfunction "1_1") (pintype "passive"))
      (node (ref "C20") (pin "1") (pinfunction "1_1") (pintype "passive"))
      (node (ref "C21") (pin "1") (pinfunction "1_1") (pintype "passive"))
      (node (ref "C22") (pin "1") (pinfunction "1_1") (pintype "passive"))
      (node (ref "C23") (pin "1") (pinfunction "1_1") (pintype "passive"))
      (node (ref "C24") (pin "1") (pinfunction "1_1") (pintype "passive"))
      (node (ref "C25") (pin "1") (pinfunction "1_1") (pintype "passive"))
      (node (ref "C27") (pin "1") (pinfunction "1_1") (pintype "passive"))
      (node (ref "C28") (pin "1") (pinfunction "1_1") (pintype "passive"))
      (node (ref "C29") (pin "1") (pinfunction "1_1") (pintype "passive"))
      (node (ref "C3") (pin "1") (pinfunction "1_1") (pintype "passive"))
      (node (ref "C30") (pin "2") (pinfunction "2_2") (pintype "passive"))
      (node (ref "C31") (pin "2") (pinfunction "2_2") (pintype "passive"))
      (node (ref "C32") (pin "2") (pinfunction "2_2") (pintype "passive"))
      (node (ref "C33") (pin "2") (pinfunction "2_2") (pintype "passive"))
      (node (ref "C4") (pin "1") (pinfunction "1_1") (pintype "passive"))
      (node (ref "C5") (pin "1") (pinfunction "1_1") (pintype "passive"))
      (node (ref "C6") (pin "1") (pinfunction "1_1") (pintype "passive"))
      (node (ref "C7") (pin "1") (pinfunction "1_1") (pintype "passive"))
      (node (ref "D1") (pin "2") (pinfunction "GND_2") (pintype "power_in"))
      (node (ref "D2") (pin "1") (pinfunction "GND_1") (pintype "power_in"))
      (node (ref "D2") (pin "4") (pinfunction "~{ON}_4") (pintype "input"))
      (node (ref "D2") (pin "5") (pinfunction "GND_5") (pintype "power_in"))
      (node (ref "D3") (pin "3") (pinfunction "A_3") (pintype "passive"))
      (node (ref "IC1") (pin "1") (pinfunction "GND_1") (pintype "power_in"))
      (node (ref "IC1") (pin "40") (pinfunction "GND_40") (pintype "power_in"))
      (node (ref "IC1") (pin "P$1") (pinfunction "GND_P$1") (pintype "power_in"))
      (node (ref "IC1") (pin "P$2") (pinfunction "GND_P$2") (pintype "power_in"))
      (node (ref "IC1") (pin "P$3") (pinfunction "GND_P$3") (pintype "power_in"))
      (node (ref "IC1") (pin "P$4") (pinfunction "GND_P$4") (pintype "power_in"))
      (node (ref "IC1") (pin "P$5") (pinfunction "GND_P$5") (pintype "power_in"))
      (node (ref "IC1") (pin "P$6") (pinfunction "GND_P$6") (pintype "power_in"))
      (node (ref "IC1") (pin "P$7") (pinfunction "GND_P$7") (pintype "power_in"))
      (node (ref "IC1") (pin "P$8") (pinfunction "GND_P$8") (pintype "power_in"))
      (node (ref "IC1") (pin "P$9") (pinfunction "GND_P$9") (pintype "power_in"))
      (node (ref "IC2") (pin "15") (pinfunction "DGND_15") (pintype "bidirectional"))
      (node (ref "IC2") (pin "2") (pinfunction "AGND_2") (pintype "bidirectional"))
      (node (ref "IC3") (pin "2") (pinfunction "GND_2") (pintype "power_in"))
      (node (ref "IC4") (pin "1") (pinfunction "GND_1") (pintype "power_in"))
      (node (ref "IC4") (pin "10") (pinfunction "GND_10") (pintype "power_in"))
      (node (ref "IC4") (pin "8") (pinfunction "GND_8") (pintype "power_in"))
      (node (ref "IC5") (pin "1") (pinfunction "GND_1") (pintype "power_in"))
      (node (ref "IC6") (pin "1") (pinfunction "GND_1") (pintype "power_in"))
      (node (ref "IC7") (pin "2") (pinfunction "GND_2") (pintype "power_in"))
      (node (ref "IC8") (pin "1") (pinfunction "GND_1") (pintype "bidirectional"))
      (node (ref "IC8") (pin "4") (pinfunction "GND_4") (pintype "bidirectional"))
      (node (ref "IC8") (pin "6") (pinfunction "QSTRT_6") (pintype "bidirectional"))
      (node (ref "IC8") (pin "TP") (pinfunction "GND_TP") (pintype "bidirectional"))
      (node (ref "IC9") (pin "A3") (pinfunction "PGND_A3") (pintype "power_in"))
      (node (ref "IC9") (pin "B3") (pinfunction "PGND_B3") (pintype "power_in"))
      (node (ref "IC9") (pin "C3") (pinfunction "PGND_C3") (pintype "power_in"))
      (node (ref "IC9") (pin "D4") (pinfunction "AGND_D4") (pintype "power_in"))
      (node (ref "J1") (pin "GND") (pinfunction "GND_GND") (pintype "power_in"))
      (node (ref "J1") (pin "GND2") (pinfunction "GND_GND2") (pintype "power_in"))
      (node (ref "J1") (pin "S@1") (pinfunction "SHIELD_S@1") (pintype "passive"))
      (node (ref "J1") (pin "S@2") (pinfunction "SHIELD_S@2") (pintype "passive"))
      (node (ref "J1") (pin "S@3") (pinfunction "SHIELD_S@3") (pintype "passive"))
      (node (ref "J1") (pin "S@4") (pinfunction "SHIELD_S@4") (pintype "passive"))
      (node (ref "J1") (pin "S@5") (pinfunction "SHIELD_S@5") (pintype "passive"))
      (node (ref "J1") (pin "S@6") (pinfunction "SHIELD_S@6") (pintype "passive"))
      (node (ref "J1") (pin "S@7") (pinfunction "SHIELD_S@7") (pintype "passive"))
      (node (ref "J1") (pin "S@8") (pinfunction "SHIELD_S@8") (pintype "passive"))
      (node (ref "J1") (pin "S@9") (pinfunction "SHIELD_S@9") (pintype "passive"))
      (node (ref "J3") (pin "2") (pinfunction "2_2") (pintype "passive"))
      (node (ref "J4") (pin "1") (pinfunction "1_1") (pintype "passive"))
      (node (ref "J5") (pin "1") (pinfunction "1_1") (pintype "passive"))
      (node (ref "J6") (pin "1") (pinfunction "1_1") (pintype "passive"))
      (node (ref "R11") (pin "1") (pinfunction "1_1") (pintype "passive"))
      (node (ref "R13") (pin "1") (pinfunction "1_1") (pintype "passive"))
      (node (ref "R14") (pin "1") (pinfunction "1_1") (pintype "passive"))
      (node (ref "R17") (pin "1") (pinfunction "1_1") (pintype "passive"))
      (node (ref "R30") (pin "1") (pinfunction "1_1") (pintype "passive"))
      (node (ref "R31") (pin "1") (pinfunction "1_1") (pintype "passive"))
      (node (ref "R37") (pin "1") (pinfunction "1_1") (pintype "passive"))
      (node (ref "R5") (pin "1") (pinfunction "1_1") (pintype "passive"))
      (node (ref "SD1") (pin "GND") (pinfunction "GND_GND") (pintype "bidirectional"))
      (node (ref "SD1") (pin "GND@1") (pinfunction "GND_GND@1") (pintype "bidirectional"))
      (node (ref "SD1") (pin "GND@2") (pinfunction "GND_GND@2") (pintype "bidirectional"))
      (node (ref "SD1") (pin "SW2") (pinfunction "SW2_SW2") (pintype "bidirectional"))
      (node (ref "SW1") (pin "1") (pinfunction "P1_1") (pintype "passive"))
      (node (ref "SW1") (pin "4") (pinfunction "P1_4") (pintype "passive"))
      (node (ref "SW2") (pin "1") (pinfunction "P1_1") (pintype "passive"))
      (node (ref "SW2") (pin "4") (pinfunction "P1_4") (pintype "passive"))
      (node (ref "SW3") (pin "1") (pinfunction "P1_1") (pintype "passive"))
      (node (ref "SW3") (pin "4") (pinfunction "P1_4") (pintype "passive"))
      (node (ref "SW4") (pin "1") (pinfunction "NO1_1") (pintype "passive"))
    )
    (net (code "29") (name "IO14") (class "Default")
      (node (ref "IC1") (pin "22") (pinfunction "IO14_22") (pintype "bidirectional"))
      (node (ref "R16") (pin "2") (pinfunction "2_2") (pintype "passive"))
    )
    (net (code "30") (name "IO48") (class "Default")
      (node (ref "IC1") (pin "25") (pinfunction "IO48_25") (pintype "bidirectional"))
      (node (ref "R8") (pin "2") (pinfunction "2_2") (pintype "passive"))
    )
    (net (code "31") (name "LED_DIN") (class "Default")
      (node (ref "D1") (pin "3") (pinfunction "DI_3") (pintype "bidirectional"))
      (node (ref "R39") (pin "2") (pinfunction "2_2") (pintype "passive"))
    )
    (net (code "32") (name "LED_LV") (class "Default")
      (node (ref "IC1") (pin "26") (pinfunction "IO45_26") (pintype "bidirectional"))
      (node (ref "R13") (pin "2") (pinfunction "2_2") (pintype "passive"))
      (node (ref "R39") (pin "1") (pinfunction "1_1") (pintype "passive"))
    )
    (net (code "33") (name "LORA_INT") (class "Default")
      (node (ref "D5") (pin "C") (pinfunction "C_C") (pintype "passive"))
      (node (ref "D6") (pin "C") (pinfunction "C_C") (pintype "passive"))
      (node (ref "IC1") (pin "36") (pinfunction "RXD0_36") (pintype "bidirectional"))
      (node (ref "R17") (pin "2") (pinfunction "2_2") (pintype "passive"))
    )
    (net (code "34") (name "LORA_RESET") (class "Default")
      (node (ref "C29") (pin "2") (pinfunction "2_2") (pintype "passive"))
      (node (ref "IC4") (pin "6") (pinfunction "~{RESET}_6") (pintype "input"))
      (node (ref "R7") (pin "1") (pinfunction "1_1") (pintype "passive"))
    )
    (net (code "35") (name "LORA_~{CS}") (class "Default")
      (node (ref "IC1") (pin "37") (pinfunction "TXD0_37") (pintype "bidirectional"))
      (node (ref "IC4") (pin "5") (pinfunction "CS_5") (pintype "input"))
    )
    (net (code "36") (name "MISO") (class "Default")
      (node (ref "IC1") (pin "33") (pinfunction "IO40_33") (pintype "bidirectional"))
      (node (ref "IC4") (pin "2") (pinfunction "MISO_2") (pintype "output"))
      (node (ref "R27") (pin "1") (pinfunction "1_1") (pintype "passive"))
      (node (ref "SD1") (pin "MISO") (pinfunction "MISO/DAT0_MISO") (pintype "bidirectional"))
    )
    (net (code "37") (name "MOSI") (class "Default")
      (node (ref "IC1") (pin "31") (pinfunction "IO38_31") (pintype "bidirectional"))
      (node (ref "IC4") (pin "3") (pinfunction "MOSI_3") (pintype "input"))
      (node (ref "R26") (pin "1") (pinfunction "1_1") (pintype "passive"))
      (node (ref "SD1") (pin "MOSI") (pinfunction "MOSI/CMD_MOSI") (pintype "bidirectional"))
    )
    (net (code "38") (name "Net-(D4-PadC)") (class "Default")
      (node (ref "D4") (pin "C") (pinfunction "C_C") (pintype "passive"))
      (node (ref "R12") (pin "2") (pinfunction "2_2") (pintype "passive"))
    )
    (net (code "39") (name "Net-(IC1-IO19)") (class "Default")
      (node (ref "IC1") (pin "13") (pinfunction "IO19_13") (pintype "bidirectional"))
      (node (ref "R33") (pin "1") (pinfunction "1_1") (pintype "passive"))
    )
    (net (code "40") (name "Net-(IC1-IO20)") (class "Default")
      (node (ref "IC1") (pin "14") (pinfunction "IO20_14") (pintype "bidirectional"))
      (node (ref "R34") (pin "1") (pinfunction "1_1") (pintype "passive"))
    )
    (net (code "41") (name "Net-(IC3-PROG)") (class "Default")
      (node (ref "IC3") (pin "5") (pinfunction "PROG_5") (pintype "input"))
      (node (ref "R11") (pin "2") (pinfunction "2_2") (pintype "passive"))
    )
    (net (code "42") (name "Net-(IC3-STAT)") (class "Default")
      (node (ref "IC3") (pin "1") (pinfunction "STAT_1") (pintype "open_collector"))
      (node (ref "R12") (pin "1") (pinfunction "1_1") (pintype "passive"))
    )
    (net (code "43") (name "Net-(IC4-ANT)") (class "Default")
      (node (ref "IC4") (pin "9") (pinfunction "ANT_9") (pintype "bidirectional"))
      (node (ref "J2") (pin "FEED") (pinfunction "SIGNAL_FEED") (pintype "bidirectional"))
    )
    (net (code "44") (name "Net-(IC4-DIO0)") (class "Default")
      (node (ref "D5") (pin "A") (pinfunction "A_A") (pintype "passive"))
      (node (ref "IC4") (pin "14") (pinfunction "DIO0_14") (pintype "bidirectional"))
    )
    (net (code "45") (name "Net-(IC4-DIO1)") (class "Default")
      (node (ref "D6") (pin "A") (pinfunction "A_A") (pintype "passive"))
      (node (ref "IC4") (pin "15") (pinfunction "DIO1_15") (pintype "bidirectional"))
    )
    (net (code "46") (name "Net-(IC5-VIN)") (class "Default")
      (node (ref "C21") (pin "2") (pinfunction "2_2") (pintype "passive"))
      (node (ref "C22") (pin "2") (pinfunction "2_2") (pintype "passive"))
      (node (ref "C24") (pin "2") (pinfunction "2_2") (pintype "passive"))
      (node (ref "IC5") (pin "3") (pinfunction "VIN_3") (pintype "power_in"))
      (node (ref "IC6") (pin "3") (pinfunction "VIN_3") (pintype "power_in"))
      (node (ref "SW4") (pin "5") (pinfunction "C2_5") (pintype "passive"))
    )
    (net (code "47") (name "Net-(IC7-C+)") (class "Default")
      (node (ref "C26") (pin "2") (pinfunction "2_2") (pintype "passive"))
      (node (ref "IC7") (pin "6") (pinfunction "C+_6") (pintype "passive"))
    )
    (net (code "48") (name "Net-(IC7-C-)") (class "Default")
      (node (ref "C26") (pin "1") (pinfunction "1_1") (pintype "passive"))
      (node (ref "IC7") (pin "4") (pinfunction "C-_4") (pintype "passive"))
    )
    (net (code "49") (name "Net-(IC9-BOLX-PadA4)") (class "Default")
      (node (ref "IC9") (pin "A4") (pinfunction "BOLX_A4") (pintype "output"))
      (node (ref "IC9") (pin "B4") (pinfunction "BOLX_B4") (pintype "output"))
      (node (ref "IC9") (pin "C4") (pinfunction "BOLX_C4") (pintype "output"))
      (node (ref "L2") (pin "1") (pinfunction "1_1") (pintype "passive"))
    )
    (net (code "50") (name "Net-(IC9-BULX-PadA2)") (class "Default")
      (node (ref "IC9") (pin "A2") (pinfunction "BULX_A2") (pintype "output"))
      (node (ref "IC9") (pin "B2") (pinfunction "BULX_B2") (pintype "output"))
      (node (ref "IC9") (pin "C2") (pinfunction "BULX_C2") (pintype "output"))
      (node (ref "L2") (pin "2") (pinfunction "2_2") (pintype "passive"))
    )
    (net (code "51") (name "Net-(IC9-CE)") (class "Default")
      (node (ref "IC9") (pin "D2") (pinfunction "CE_D2") (pintype "input"))
      (node (ref "R1") (pin "1") (pinfunction "1_1") (pintype "passive"))
    )
    (net (code "52") (name "Net-(J1-CC1)") (class "Default")
      (node (ref "J1") (pin "A5") (pinfunction "CC1_A5") (pintype "bidirectional"))
      (node (ref "R30") (pin "2") (pinfunction "2_2") (pintype "passive"))
    )
    (net (code "53") (name "Net-(J1-CC2)") (class "Default")
      (node (ref "J1") (pin "B5") (pinfunction "CC2_B5") (pintype "bidirectional"))
      (node (ref "R31") (pin "2") (pinfunction "2_2") (pintype "passive"))
    )
    (net (code "54") (name "Net-(J2-GND-Pad1)") (class "Default")
      (node (ref "J2") (pin "1") (pinfunction "GND_1") (pintype "bidirectional"))
      (node (ref "J2") (pin "2") (pinfunction "GND_2") (pintype "bidirectional"))
      (node (ref "R37") (pin "2") (pinfunction "2_2") (pintype "passive"))
    )
    (net (code "55") (name "Net-(J6-Pad3)") (class "Default")
      (node (ref "J6") (pin "3") (pinfunction "3_3") (pintype "passive"))
      (node (ref "R8") (pin "1") (pinfunction "1_1") (pintype "passive"))
    )
    (net (code "56") (name "Net-(J6-Pad4)") (class "Default")
      (node (ref "J6") (pin "4") (pinfunction "4_4") (pintype "passive"))
      (node (ref "R16") (pin "1") (pinfunction "1_1") (pintype "passive"))
    )
    (net (code "57") (name "SCK") (class "Default")
      (node (ref "IC1") (pin "32") (pinfunction "IO39_32") (pintype "bidirectional"))
      (node (ref "IC4") (pin "4") (pinfunction "SCK_4") (pintype "input"))
      (node (ref "R28") (pin "1") (pinfunction "1_1") (pintype "passive"))
      (node (ref "SD1") (pin "SCK") (pinfunction "SCK_SCK") (pintype "bidirectional"))
    )
    (net (code "58") (name "SCL") (class "Default")
      (node (ref "IC1") (pin "39") (pinfunction "IO1_39") (pintype "bidirectional"))
      (node (ref "IC8") (pin "7") (pinfunction "SCL_7") (pintype "bidirectional"))
      (node (ref "J4") (pin "4") (pinfunction "4_4") (pintype "passive"))
      (node (ref "R10") (pin "2") (pinfunction "2_2") (pintype "passive"))
    )
    (net (code "59") (name "SDA") (class "Default")
      (node (ref "IC1") (pin "38") (pinfunction "IO2_38") (pintype "bidirectional"))
      (node (ref "IC8") (pin "8") (pinfunction "SDA_8") (pintype "bidirectional"))
      (node (ref "J4") (pin "3") (pinfunction "3_3") (pintype "passive"))
      (node (ref "R9") (pin "2") (pinfunction "2_2") (pintype "passive"))
    )
    (net (code "60") (name "SDIO_3V3") (class "Default")
      (node (ref "C6") (pin "2") (pinfunction "2_2") (pintype "passive"))
      (node (ref "C7") (pin "2") (pinfunction "2_2") (pintype "passive"))
      (node (ref "Q2") (pin "3") (pinfunction "D_3") (pintype "passive"))
      (node (ref "R26") (pin "2") (pinfunction "2_2") (pintype "passive"))
      (node (ref "R27") (pin "2") (pinfunction "2_2") (pintype "passive"))
      (node (ref "R28") (pin "2") (pinfunction "2_2") (pintype "passive"))
      (node (ref "R29") (pin "2") (pinfunction "2_2") (pintype "passive"))
      (node (ref "SD1") (pin "VCC") (pinfunction "3V3_VCC") (pintype "bidirectional"))
    )
    (net (code "61") (name "SD_ENABLE") (class "Default")
      (node (ref "IC1") (pin "15") (pinfunction "IO3_15") (pintype "bidirectional"))
      (node (ref "Q2") (pin "1") (pinfunction "G_1") (pintype "passive"))
    )
    (net (code "62") (name "SD_SW") (class "Default")
      (node (ref "IC1") (pin "35") (pinfunction "IO42_35") (pintype "bidirectional"))
      (node (ref "R6") (pin "1") (pinfunction "1_1") (pintype "passive"))
      (node (ref "SD1") (pin "SW1") (pinfunction "SW1_SW1") (pintype "bidirectional"))
    )
    (net (code "63") (name "SD_~{CS}") (class "Default")
      (node (ref "IC1") (pin "34") (pinfunction "IO41_34") (pintype "bidirectional"))
      (node (ref "R29") (pin "1") (pinfunction "1_1") (pintype "passive"))
      (node (ref "SD1") (pin "CS") (pinfunction "~{CS}/DAT3_CS") (pintype "bidirectional"))
    )
    (net (code "64") (name "USB-DN") (class "Default")
      (node (ref "D3") (pin "1") (pinfunction "C1_1") (pintype "passive"))
      (node (ref "J1") (pin "A7") (pinfunction "D-_A7") (pintype "bidirectional"))
      (node (ref "J1") (pin "B7") (pinfunction "D-_B7") (pintype "bidirectional"))
      (node (ref "R33") (pin "2") (pinfunction "2_2") (pintype "passive"))
    )
    (net (code "65") (name "USB-DP") (class "Default")
      (node (ref "D3") (pin "2") (pinfunction "C2_2") (pintype "passive"))
      (node (ref "J1") (pin "A6") (pinfunction "D+_A6") (pintype "bidirectional"))
      (node (ref "J1") (pin "B6") (pinfunction "D+_B6") (pintype "bidirectional"))
      (node (ref "R34") (pin "2") (pinfunction "2_2") (pintype "passive"))
    )
    (net (code "66") (name "VBAT") (class "Default")
      (node (ref "C16") (pin "2") (pinfunction "2_2") (pintype "passive"))
      (node (ref "C17") (pin "2") (pinfunction "2_2") (pintype "passive"))
      (node (ref "D2") (pin "6") (pinfunction "VIN2_6") (pintype "power_in"))
      (node (ref "IC3") (pin "3") (pinfunction "VBAT_3") (pintype "bidirectional"))
      (node (ref "IC8") (pin "2") (pinfunction "CELL_2") (pintype "bidirectional"))
      (node (ref "IC8") (pin "3") (pinfunction "VCC_3") (pintype "bidirectional"))
      (node (ref "J3") (pin "1") (pinfunction "1_1") (pintype "passive"))
    )
    (net (code "67") (name "VSWITCHED") (class "Default")
      (node (ref "C25") (pin "2") (pinfunction "2_2") (pintype "passive"))
      (node (ref "C32") (pin "1") (pinfunction "1_1") (pintype "passive"))
      (node (ref "C33") (pin "1") (pinfunction "1_1") (pintype "passive"))
      (node (ref "D2") (pin "2") (pinfunction "VOUT_2") (pintype "power_in"))
      (node (ref "D2") (pin "7") (pinfunction "VOUT_7") (pintype "power_in"))
      (node (ref "IC7") (pin "5") (pinfunction "VIN_5") (pintype "power_in"))
      (node (ref "IC9") (pin "A1") (pinfunction "PVIN_A1") (pintype "power_in"))
      (node (ref "IC9") (pin "B1") (pinfunction "PVIN_B1") (pintype "power_in"))
      (node (ref "IC9") (pin "C1") (pinfunction "PVIN_C1") (pintype "power_in"))
      (node (ref "IC9") (pin "D1") (pinfunction "AVIN_D1") (pintype "power_in"))
      (node (ref "IC9") (pin "D3") (pinfunction "MODE_D3") (pintype "input"))
      (node (ref "SW4") (pin "3") (pinfunction "NC1_3") (pintype "passive"))
      (node (ref "SW4") (pin "6") (pinfunction "NC2_6") (pintype "passive"))
    )
    (net (code "68") (name "VUSB") (class "Default")
      (node (ref "C23") (pin "2") (pinfunction "2_2") (pintype "passive"))
      (node (ref "C28") (pin "2") (pinfunction "2_2") (pintype "passive"))
      (node (ref "D2") (pin "3") (pinfunction "VIN1_3") (pintype "power_in"))
      (node (ref "D4") (pin "A") (pinfunction "A_A") (pintype "passive"))
      (node (ref "IC3") (pin "4") (pinfunction "VIN_4") (pintype "power_in"))
      (node (ref "J1") (pin "VBUS") (pinfunction "VBUS_VBUS") (pintype "power_in"))
      (node (ref "J1") (pin "VBUS2") (pinfunction "VBUS_VBUS2") (pintype "power_in"))
    )
    (net (code "69") (name "V_LED") (class "Default")
      (node (ref "C18") (pin "2") (pinfunction "2_2") (pintype "passive"))
      (node (ref "D1") (pin "4") (pinfunction "VCC_4") (pintype "power_in"))
      (node (ref "R1") (pin "2") (pinfunction "2_2") (pintype "passive"))
      (node (ref "SW4") (pin "2") (pinfunction "C1_2") (pintype "passive"))
    )
    (net (code "70") (name "unconnected-(D1-DO-Pad1)") (class "Default")
      (node (ref "D1") (pin "1") (pinfunction "DO_1") (pintype "bidirectional"))
    )
    (net (code "71") (name "unconnected-(D2-ST-Pad8)") (class "Default")
      (node (ref "D2") (pin "8") (pinfunction "ST_8") (pintype "open_collector"))
    )
    (net (code "72") (name "unconnected-(IC1-IO35-Pad28)") (class "Default")
      (node (ref "IC1") (pin "28") (pinfunction "IO35_28") (pintype "bidirectional"))
    )
    (net (code "73") (name "unconnected-(IC1-IO36-Pad29)") (class "Default")
      (node (ref "IC1") (pin "29") (pinfunction "IO36_29") (pintype "bidirectional"))
    )
    (net (code "74") (name "unconnected-(IC1-IO37-Pad30)") (class "Default")
      (node (ref "IC1") (pin "30") (pinfunction "IO37_30") (pintype "bidirectional"))
    )
    (net (code "75") (name "unconnected-(IC2-NC1-Pad1)") (class "Default")
      (node (ref "IC2") (pin "1") (pinfunction "NC1_1") (pintype "bidirectional"))
    )
    (net (code "76") (name "unconnected-(IC2-Y0-Pad24)") (class "Default")
      (node (ref "IC2") (pin "24") (pinfunction "Y0_24") (pintype "bidirectional"))
    )
    (net (code "77") (name "unconnected-(IC2-Y1-Pad23)") (class "Default")
      (node (ref "IC2") (pin "23") (pinfunction "Y1_23") (pintype "bidirectional"))
    )
    (net (code "78") (name "unconnected-(IC4-DIO2-Pad16)") (class "Default")
      (node (ref "IC4") (pin "16") (pinfunction "DIO2_16") (pintype "bidirectional"))
    )
    (net (code "79") (name "unconnected-(IC4-DIO3-Pad11)") (class "Default")
      (node (ref "IC4") (pin "11") (pinfunction "DIO3_11") (pintype "bidirectional"))
    )
    (net (code "80") (name "unconnected-(IC4-DIO4-Pad12)") (class "Default")
      (node (ref "IC4") (pin "12") (pinfunction "DIO4_12") (pintype "bidirectional"))
    )
    (net (code "81") (name "unconnected-(IC4-DIO5-Pad7)") (class "Default")
      (node (ref "IC4") (pin "7") (pinfunction "DIO5_7") (pintype "bidirectional"))
    )
    (net (code "82") (name "unconnected-(IC8-~{ALERT}-Pad5)") (class "Default")
      (node (ref "IC8") (pin "5") (pinfunction "~{ALERT}_5") (pintype "bidirectional"))
    )
    (net (code "83") (name "unconnected-(SD1-PadDAT1)") (class "Default")
      (node (ref "SD1") (pin "DAT1") (pinfunction "DAT1_DAT1") (pintype "bidirectional"))
    )
    (net (code "84") (name "unconnected-(SD1-PadDAT2)") (class "Default")
      (node (ref "SD1") (pin "DAT2") (pinfunction "DAT2_DAT2") (pintype "bidirectional"))
    )
    (net (code "85") (name "unconnected-(SW4-NO2-Pad4)") (class "Default")
      (node (ref "SW4") (pin "4") (pinfunction "NO2_4") (pintype "passive"))
    )
  )
)
